# StupidPower2.net
KiCad netlist of a schematic drawn in EAGLE
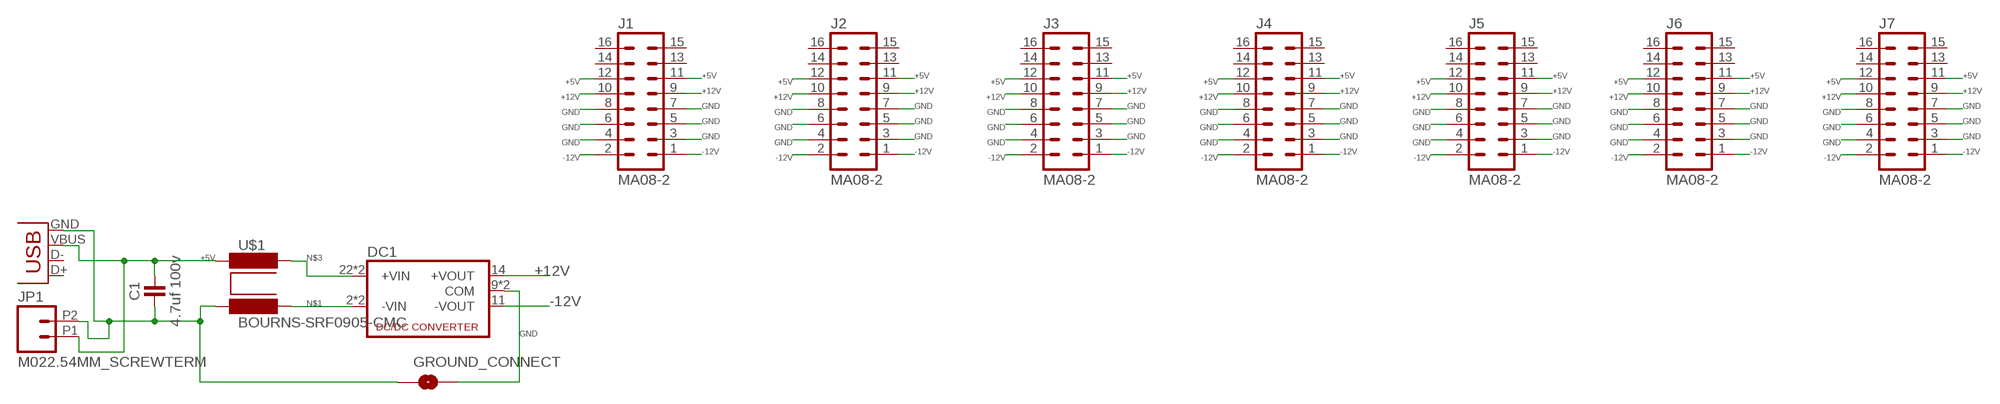
[diagram p0: schematic, sheet 1]

(export (version "E")
  (design (tool "Eeschema 10.0.6"))
  (components
    (comp (ref "C1")
      (value "4.7uf 100v")
      (footprint "eagle-import:C1206")
      (libsource (lib "eagle-import") (part "CAPACITOR-1206"))
    )
    (comp (ref "DC1")
      (value "XPOWER-JCA")
      (footprint "eagle-import:XP-POWER_JCA")
      (libsource (lib "eagle-import") (part "XPOWER-JCA"))
    )
    (comp (ref "GROUND_CONNECT")
      (value "SOLDERJUMPERNO")
      (footprint "eagle-import:SJ_2S-NO")
      (libsource (lib "eagle-import") (part "SOLDERJUMPERNO"))
    )
    (comp (ref "J1")
      (value "MA08-2")
      (footprint "eagle-import:MA08-2")
      (libsource (lib "eagle-import") (part "MA08-2"))
    )
    (comp (ref "J2")
      (value "MA08-2")
      (footprint "eagle-import:MA08-2")
      (libsource (lib "eagle-import") (part "MA08-2"))
    )
    (comp (ref "J3")
      (value "MA08-2")
      (footprint "eagle-import:MA08-2")
      (libsource (lib "eagle-import") (part "MA08-2"))
    )
    (comp (ref "J4")
      (value "MA08-2")
      (footprint "eagle-import:MA08-2")
      (libsource (lib "eagle-import") (part "MA08-2"))
    )
    (comp (ref "J5")
      (value "MA08-2")
      (footprint "eagle-import:MA08-2")
      (libsource (lib "eagle-import") (part "MA08-2"))
    )
    (comp (ref "J6")
      (value "MA08-2")
      (footprint "eagle-import:MA08-2")
      (libsource (lib "eagle-import") (part "MA08-2"))
    )
    (comp (ref "J7")
      (value "MA08-2")
      (footprint "eagle-import:MA08-2")
      (libsource (lib "eagle-import") (part "MA08-2"))
    )
    (comp (ref "JP1")
      (value "M022.54MM_SCREWTERM")
      (footprint "eagle-import:1X02_2.54_SCREWTERM")
      (libsource (lib "eagle-import") (part "M022.54MM_SCREWTERM"))
    )
    (comp (ref "JP2")
      (value "USB-B")
      (footprint "eagle-import:USB-B-PTH")
      (libsource (lib "eagle-import") (part "USBPTH"))
    )
    (comp (ref "U$1")
      (value "BOURNS-SRF0905-CMC")
      (footprint "eagle-import:BOURNS-SRF0905-LINEFILTER")
      (libsource (lib "eagle-import") (part "BOURNS-SRF0905-CMC"))
    )
  )
  (nets
    (net (code "1") (name "/+5V") (class "Default")
      (node (ref "C1") (pin "2") (pinfunction "2_2") (pintype "passive"))
      (node (ref "J1") (pin "11") (pinfunction "11_11") (pintype "passive"))
      (node (ref "J1") (pin "12") (pinfunction "12_12") (pintype "passive"))
      (node (ref "J2") (pin "11") (pinfunction "11_11") (pintype "passive"))
      (node (ref "J2") (pin "12") (pinfunction "12_12") (pintype "passive"))
      (node (ref "J3") (pin "11") (pinfunction "11_11") (pintype "passive"))
      (node (ref "J3") (pin "12") (pinfunction "12_12") (pintype "passive"))
      (node (ref "J4") (pin "11") (pinfunction "11_11") (pintype "passive"))
      (node (ref "J4") (pin "12") (pinfunction "12_12") (pintype "passive"))
      (node (ref "J5") (pin "11") (pinfunction "11_11") (pintype "passive"))
      (node (ref "J5") (pin "12") (pinfunction "12_12") (pintype "passive"))
      (node (ref "J6") (pin "11") (pinfunction "11_11") (pintype "passive"))
      (node (ref "J6") (pin "12") (pinfunction "12_12") (pintype "passive"))
      (node (ref "J7") (pin "11") (pinfunction "11_11") (pintype "passive"))
      (node (ref "J7") (pin "12") (pinfunction "12_12") (pintype "passive"))
      (node (ref "JP1") (pin "P1") (pinfunction "1_P1") (pintype "passive"))
      (node (ref "JP2") (pin "VBUS") (pinfunction "VBUS_VBUS") (pintype "bidirectional"))
      (node (ref "U$1") (pin "2") (pinfunction "2_2") (pintype "passive"))
    )
    (net (code "2") (name "/+12V") (class "Default")
      (node (ref "DC1") (pin "14") (pinfunction "+VOUT_14") (pintype "passive"))
      (node (ref "J1") (pin "10") (pinfunction "10_10") (pintype "passive"))
      (node (ref "J1") (pin "9") (pinfunction "9_9") (pintype "passive"))
      (node (ref "J2") (pin "10") (pinfunction "10_10") (pintype "passive"))
      (node (ref "J2") (pin "9") (pinfunction "9_9") (pintype "passive"))
      (node (ref "J3") (pin "10") (pinfunction "10_10") (pintype "passive"))
      (node (ref "J3") (pin "9") (pinfunction "9_9") (pintype "passive"))
      (node (ref "J4") (pin "10") (pinfunction "10_10") (pintype "passive"))
      (node (ref "J4") (pin "9") (pinfunction "9_9") (pintype "passive"))
      (node (ref "J5") (pin "10") (pinfunction "10_10") (pintype "passive"))
      (node (ref "J5") (pin "9") (pinfunction "9_9") (pintype "passive"))
      (node (ref "J6") (pin "10") (pinfunction "10_10") (pintype "passive"))
      (node (ref "J6") (pin "9") (pinfunction "9_9") (pintype "passive"))
      (node (ref "J7") (pin "10") (pinfunction "10_10") (pintype "passive"))
      (node (ref "J7") (pin "9") (pinfunction "9_9") (pintype "passive"))
    )
    (net (code "3") (name "/-12V") (class "Default")
      (node (ref "DC1") (pin "11") (pinfunction "-VOUT_11") (pintype "passive"))
      (node (ref "J1") (pin "1") (pinfunction "1_1") (pintype "passive"))
      (node (ref "J1") (pin "2") (pinfunction "2_2") (pintype "passive"))
      (node (ref "J2") (pin "1") (pinfunction "1_1") (pintype "passive"))
      (node (ref "J2") (pin "2") (pinfunction "2_2") (pintype "passive"))
      (node (ref "J3") (pin "1") (pinfunction "1_1") (pintype "passive"))
      (node (ref "J3") (pin "2") (pinfunction "2_2") (pintype "passive"))
      (node (ref "J4") (pin "1") (pinfunction "1_1") (pintype "passive"))
      (node (ref "J4") (pin "2") (pinfunction "2_2") (pintype "passive"))
      (node (ref "J5") (pin "1") (pinfunction "1_1") (pintype "passive"))
      (node (ref "J5") (pin "2") (pinfunction "2_2") (pintype "passive"))
      (node (ref "J6") (pin "1") (pinfunction "1_1") (pintype "passive"))
      (node (ref "J6") (pin "2") (pinfunction "2_2") (pintype "passive"))
      (node (ref "J7") (pin "1") (pinfunction "1_1") (pintype "passive"))
      (node (ref "J7") (pin "2") (pinfunction "2_2") (pintype "passive"))
    )
    (net (code "4") (name "/GND") (class "Default")
      (node (ref "DC1") (pin "16") (pinfunction "COM_16") (pintype "passive"))
      (node (ref "DC1") (pin "9") (pinfunction "COM_9") (pintype "passive"))
      (node (ref "GROUND_CONNECT") (pin "2") (pinfunction "2_2") (pintype "passive"))
      (node (ref "J1") (pin "3") (pinfunction "3_3") (pintype "passive"))
      (node (ref "J1") (pin "4") (pinfunction "4_4") (pintype "passive"))
      (node (ref "J1") (pin "5") (pinfunction "5_5") (pintype "passive"))
      (node (ref "J1") (pin "6") (pinfunction "6_6") (pintype "passive"))
      (node (ref "J1") (pin "7") (pinfunction "7_7") (pintype "passive"))
      (node (ref "J1") (pin "8") (pinfunction "8_8") (pintype "passive"))
      (node (ref "J2") (pin "3") (pinfunction "3_3") (pintype "passive"))
      (node (ref "J2") (pin "4") (pinfunction "4_4") (pintype "passive"))
      (node (ref "J2") (pin "5") (pinfunction "5_5") (pintype "passive"))
      (node (ref "J2") (pin "6") (pinfunction "6_6") (pintype "passive"))
      (node (ref "J2") (pin "7") (pinfunction "7_7") (pintype "passive"))
      (node (ref "J2") (pin "8") (pinfunction "8_8") (pintype "passive"))
      (node (ref "J3") (pin "3") (pinfunction "3_3") (pintype "passive"))
      (node (ref "J3") (pin "4") (pinfunction "4_4") (pintype "passive"))
      (node (ref "J3") (pin "5") (pinfunction "5_5") (pintype "passive"))
      (node (ref "J3") (pin "6") (pinfunction "6_6") (pintype "passive"))
      (node (ref "J3") (pin "7") (pinfunction "7_7") (pintype "passive"))
      (node (ref "J3") (pin "8") (pinfunction "8_8") (pintype "passive"))
      (node (ref "J4") (pin "3") (pinfunction "3_3") (pintype "passive"))
      (node (ref "J4") (pin "4") (pinfunction "4_4") (pintype "passive"))
      (node (ref "J4") (pin "5") (pinfunction "5_5") (pintype "passive"))
      (node (ref "J4") (pin "6") (pinfunction "6_6") (pintype "passive"))
      (node (ref "J4") (pin "7") (pinfunction "7_7") (pintype "passive"))
      (node (ref "J4") (pin "8") (pinfunction "8_8") (pintype "passive"))
      (node (ref "J5") (pin "3") (pinfunction "3_3") (pintype "passive"))
      (node (ref "J5") (pin "4") (pinfunction "4_4") (pintype "passive"))
      (node (ref "J5") (pin "5") (pinfunction "5_5") (pintype "passive"))
      (node (ref "J5") (pin "6") (pinfunction "6_6") (pintype "passive"))
      (node (ref "J5") (pin "7") (pinfunction "7_7") (pintype "passive"))
      (node (ref "J5") (pin "8") (pinfunction "8_8") (pintype "passive"))
      (node (ref "J6") (pin "3") (pinfunction "3_3") (pintype "passive"))
      (node (ref "J6") (pin "4") (pinfunction "4_4") (pintype "passive"))
      (node (ref "J6") (pin "5") (pinfunction "5_5") (pintype "passive"))
      (node (ref "J6") (pin "6") (pinfunction "6_6") (pintype "passive"))
      (node (ref "J6") (pin "7") (pinfunction "7_7") (pintype "passive"))
      (node (ref "J6") (pin "8") (pinfunction "8_8") (pintype "passive"))
      (node (ref "J7") (pin "3") (pinfunction "3_3") (pintype "passive"))
      (node (ref "J7") (pin "4") (pinfunction "4_4") (pintype "passive"))
      (node (ref "J7") (pin "5") (pinfunction "5_5") (pintype "passive"))
      (node (ref "J7") (pin "6") (pinfunction "6_6") (pintype "passive"))
      (node (ref "J7") (pin "7") (pinfunction "7_7") (pintype "passive"))
      (node (ref "J7") (pin "8") (pinfunction "8_8") (pintype "passive"))
    )
    (net (code "5") (name "/N$1") (class "Default")
      (node (ref "DC1") (pin "2") (pinfunction "-VIN_2") (pintype "passive"))
      (node (ref "DC1") (pin "3") (pinfunction "-VIN_3") (pintype "passive"))
      (node (ref "U$1") (pin "4") (pinfunction "4_4") (pintype "passive"))
    )
    (net (code "6") (name "/N$3") (class "Default")
      (node (ref "DC1") (pin "22") (pinfunction "+VIN_22") (pintype "passive"))
      (node (ref "DC1") (pin "23") (pinfunction "+VIN_23") (pintype "passive"))
      (node (ref "U$1") (pin "3") (pinfunction "3_3") (pintype "passive"))
    )
    (net (code "7") (name "Net-(JP1-2)") (class "Default")
      (node (ref "C1") (pin "1") (pinfunction "1_1") (pintype "passive"))
      (node (ref "GROUND_CONNECT") (pin "1") (pinfunction "1_1") (pintype "passive"))
      (node (ref "JP1") (pin "P2") (pinfunction "2_P2") (pintype "passive"))
      (node (ref "JP2") (pin "GND") (pinfunction "GND_GND") (pintype "bidirectional"))
      (node (ref "U$1") (pin "1") (pinfunction "1_1") (pintype "passive"))
    )
    (net (code "8") (name "unconnected-(J1-Pad13)") (class "Default")
      (node (ref "J1") (pin "13") (pinfunction "13_13") (pintype "passive"))
    )
    (net (code "9") (name "unconnected-(J1-Pad14)") (class "Default")
      (node (ref "J1") (pin "14") (pinfunction "14_14") (pintype "passive"))
    )
    (net (code "10") (name "unconnected-(J1-Pad15)") (class "Default")
      (node (ref "J1") (pin "15") (pinfunction "15_15") (pintype "passive"))
    )
    (net (code "11") (name "unconnected-(J1-Pad16)") (class "Default")
      (node (ref "J1") (pin "16") (pinfunction "16_16") (pintype "passive"))
    )
    (net (code "12") (name "unconnected-(J2-Pad13)") (class "Default")
      (node (ref "J2") (pin "13") (pinfunction "13_13") (pintype "passive"))
    )
    (net (code "13") (name "unconnected-(J2-Pad14)") (class "Default")
      (node (ref "J2") (pin "14") (pinfunction "14_14") (pintype "passive"))
    )
    (net (code "14") (name "unconnected-(J2-Pad15)") (class "Default")
      (node (ref "J2") (pin "15") (pinfunction "15_15") (pintype "passive"))
    )
    (net (code "15") (name "unconnected-(J2-Pad16)") (class "Default")
      (node (ref "J2") (pin "16") (pinfunction "16_16") (pintype "passive"))
    )
    (net (code "16") (name "unconnected-(J3-Pad13)") (class "Default")
      (node (ref "J3") (pin "13") (pinfunction "13_13") (pintype "passive"))
    )
    (net (code "17") (name "unconnected-(J3-Pad14)") (class "Default")
      (node (ref "J3") (pin "14") (pinfunction "14_14") (pintype "passive"))
    )
    (net (code "18") (name "unconnected-(J3-Pad15)") (class "Default")
      (node (ref "J3") (pin "15") (pinfunction "15_15") (pintype "passive"))
    )
    (net (code "19") (name "unconnected-(J3-Pad16)") (class "Default")
      (node (ref "J3") (pin "16") (pinfunction "16_16") (pintype "passive"))
    )
    (net (code "20") (name "unconnected-(J4-Pad13)") (class "Default")
      (node (ref "J4") (pin "13") (pinfunction "13_13") (pintype "passive"))
    )
    (net (code "21") (name "unconnected-(J4-Pad14)") (class "Default")
      (node (ref "J4") (pin "14") (pinfunction "14_14") (pintype "passive"))
    )
    (net (code "22") (name "unconnected-(J4-Pad15)") (class "Default")
      (node (ref "J4") (pin "15") (pinfunction "15_15") (pintype "passive"))
    )
    (net (code "23") (name "unconnected-(J4-Pad16)") (class "Default")
      (node (ref "J4") (pin "16") (pinfunction "16_16") (pintype "passive"))
    )
    (net (code "24") (name "unconnected-(J5-Pad13)") (class "Default")
      (node (ref "J5") (pin "13") (pinfunction "13_13") (pintype "passive"))
    )
    (net (code "25") (name "unconnected-(J5-Pad14)") (class "Default")
      (node (ref "J5") (pin "14") (pinfunction "14_14") (pintype "passive"))
    )
    (net (code "26") (name "unconnected-(J5-Pad15)") (class "Default")
      (node (ref "J5") (pin "15") (pinfunction "15_15") (pintype "passive"))
    )
    (net (code "27") (name "unconnected-(J5-Pad16)") (class "Default")
      (node (ref "J5") (pin "16") (pinfunction "16_16") (pintype "passive"))
    )
    (net (code "28") (name "unconnected-(J6-Pad13)") (class "Default")
      (node (ref "J6") (pin "13") (pinfunction "13_13") (pintype "passive"))
    )
    (net (code "29") (name "unconnected-(J6-Pad14)") (class "Default")
      (node (ref "J6") (pin "14") (pinfunction "14_14") (pintype "passive"))
    )
    (net (code "30") (name "unconnected-(J6-Pad15)") (class "Default")
      (node (ref "J6") (pin "15") (pinfunction "15_15") (pintype "passive"))
    )
    (net (code "31") (name "unconnected-(J6-Pad16)") (class "Default")
      (node (ref "J6") (pin "16") (pinfunction "16_16") (pintype "passive"))
    )
    (net (code "32") (name "unconnected-(J7-Pad13)") (class "Default")
      (node (ref "J7") (pin "13") (pinfunction "13_13") (pintype "passive"))
    )
    (net (code "33") (name "unconnected-(J7-Pad14)") (class "Default")
      (node (ref "J7") (pin "14") (pinfunction "14_14") (pintype "passive"))
    )
    (net (code "34") (name "unconnected-(J7-Pad15)") (class "Default")
      (node (ref "J7") (pin "15") (pinfunction "15_15") (pintype "passive"))
    )
    (net (code "35") (name "unconnected-(J7-Pad16)") (class "Default")
      (node (ref "J7") (pin "16") (pinfunction "16_16") (pintype "passive"))
    )
    (net (code "36") (name "unconnected-(JP2-PadD+)") (class "Default")
      (node (ref "JP2") (pin "D+") (pinfunction "D+_D+") (pintype "bidirectional"))
    )
    (net (code "37") (name "unconnected-(JP2-PadD-)") (class "Default")
      (node (ref "JP2") (pin "D-") (pinfunction "D-_D-") (pintype "bidirectional"))
    )
  )
)
